# Power_Nichrome.net
KiCad netlist of a schematic drawn in Altium Designer
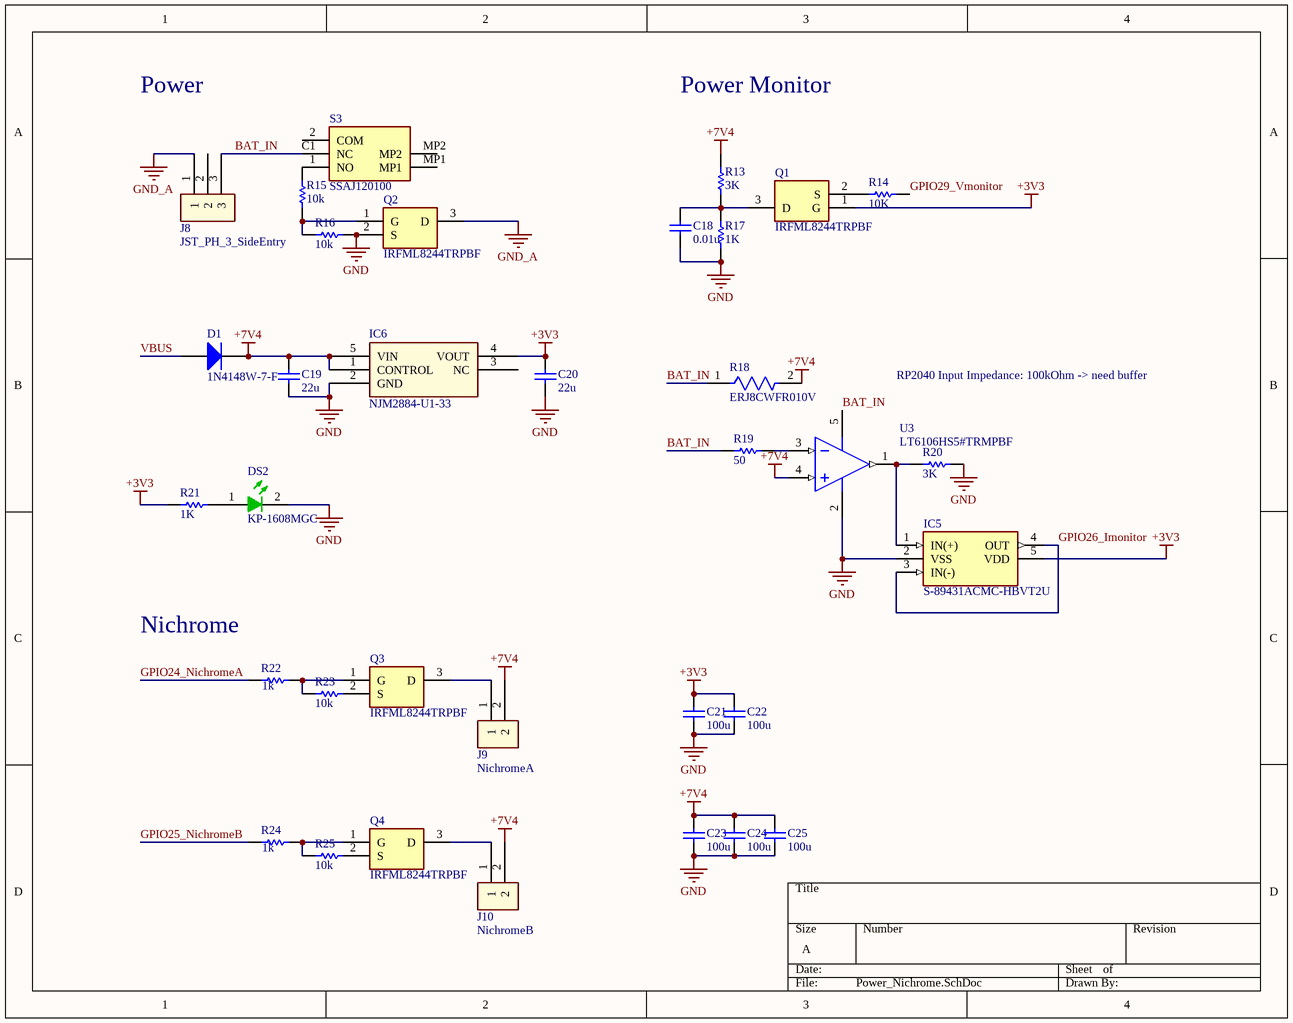
[diagram p0: Power_Nichrome.SchDoc]

(export (version "E")
  (design (tool "Eeschema 10.0.6"))
  (components
    (comp (ref "C18")
      (value "0.01u")
      (footprint "1608[0603]")
      (description "Capacitor")
      (libsource (lib "Simulation Generic Components") (part "Capacitor"))
    )
    (comp (ref "C19")
      (value "22u")
      (footprint "1608[0603]")
      (description "Capacitor")
      (libsource (lib "Simulation Generic Components") (part "Capacitor"))
    )
    (comp (ref "C20")
      (value "22u")
      (footprint "1608[0603]")
      (description "Capacitor")
      (libsource (lib "Simulation Generic Components") (part "Capacitor"))
    )
    (comp (ref "C21")
      (value "100u")
      (footprint "1608[0603]")
      (description "Capacitor")
      (libsource (lib "Simulation Generic Components") (part "Capacitor"))
    )
    (comp (ref "C22")
      (value "100u")
      (footprint "1608[0603]")
      (description "Capacitor")
      (libsource (lib "Simulation Generic Components") (part "Capacitor"))
    )
    (comp (ref "C23")
      (value "100u")
      (footprint "1608[0603]")
      (description "Capacitor")
      (libsource (lib "Simulation Generic Components") (part "Capacitor"))
    )
    (comp (ref "C24")
      (value "100u")
      (footprint "1608[0603]")
      (description "Capacitor")
      (libsource (lib "Simulation Generic Components") (part "Capacitor"))
    )
    (comp (ref "C25")
      (value "100u")
      (footprint "1608[0603]")
      (description "Capacitor")
      (libsource (lib "Simulation Generic Components") (part "Capacitor"))
    )
    (comp (ref "D1")
      (value "1N4148W-7-F")
      (footprint "DIOD-SOD123-2_V")
      (description "Fast Switching Diode, 100 V, 0.15 A, -65 to 150 degC, 2-Pin?SOD123, RoHS, Tape and Reel")
      (fields (field (name "MANUFACTURER") "DiodesIncorporated"))
      (libsource (lib "Altium Content Vault") (part "D-AK-2"))
    )
    (comp (ref "DS2")
      (value "KP-1608MGC")
      (footprint "KING-0603LED_GREEN_V")
      (description "LED, SMT, 0603(1608), 1.1mm thickness, Green")
      (fields (field (name "MANUFACTURER") "Kingbright"))
      (libsource (lib "Altium Content Vault") (part "KING-LED-GREEN-A1K2-2"))
    )
    (comp (ref "IC5")
      (value "S-89431ACMC-HBVT2U")
      (footprint "SamacSys:SOT95P275X130-5N")
      (description "Integrated Circuit")
      (fields (field (name "MOUSER PART NUMBER") "628-S89431ACMCHBVT2G"))
      (libsource (lib "*") (part "S-89431ACMC-HBVT2U"))
    )
    (comp (ref "IC6")
      (value "NJM2884-U1-33")
      (footprint "NJM2884-U1-33")
      (libsource (lib "tanekonsat_lib") (part "NJM2884-U1-33"))
    )
    (comp (ref "J8")
      (value "JST_PH_3_SideEntry")
      (footprint "JST_PH_3_SideEntry")
      (libsource (lib "tanekonsat_lib") (part "JST_PH_3_SideEntry"))
    )
    (comp (ref "J9")
      (value "NichromeA")
      (footprint "PinHeader_2.0_2_SMD")
      (libsource (lib "tanekonsat_lib") (part "PinHeader_2.0_2_SMD"))
    )
    (comp (ref "J10")
      (value "NichromeB")
      (footprint "PinHeader_2.0_2_SMD")
      (libsource (lib "tanekonsat_lib") (part "PinHeader_2.0_2_SMD"))
    )
    (comp (ref "Q1")
      (value "IRFML8244TRPBF")
      (footprint "SamacSys:SOT95P237X112-3N")
      (description "Transistor")
      (fields (field (name "MOUSER PART NUMBER") "942-IRFML8244TRPBF"))
      (libsource (lib "") (part "IRFML8244TRPBF_1"))
    )
    (comp (ref "Q2")
      (value "IRFML8244TRPBF")
      (footprint "SamacSys:SOT95P237X112-3N")
      (description "Transistor")
      (fields (field (name "MOUSER PART NUMBER") "942-IRFML8244TRPBF"))
      (libsource (lib "*") (part "IRFML8244TRPBF"))
    )
    (comp (ref "Q3")
      (value "IRFML8244TRPBF")
      (footprint "SamacSys:SOT95P237X112-3N")
      (description "Transistor")
      (fields (field (name "MOUSER PART NUMBER") "942-IRFML8244TRPBF"))
      (libsource (lib "*") (part "IRFML8244TRPBF"))
    )
    (comp (ref "Q4")
      (value "IRFML8244TRPBF")
      (footprint "SamacSys:SOT95P237X112-3N")
      (description "Transistor")
      (fields (field (name "MOUSER PART NUMBER") "942-IRFML8244TRPBF"))
      (libsource (lib "*") (part "IRFML8244TRPBF"))
    )
    (comp (ref "R13")
      (value "3K")
      (footprint "1608[0603]")
      (description "Resistor")
      (libsource (lib "Simulation Generic Components") (part "Resistor"))
    )
    (comp (ref "R14")
      (value "10K")
      (footprint "1608[0603]")
      (description "Resistor")
      (libsource (lib "Simulation Generic Components") (part "Resistor"))
    )
    (comp (ref "R15")
      (value "10k")
      (footprint "1608[0603]")
      (description "Resistor")
      (libsource (lib "Simulation Generic Components") (part "Resistor"))
    )
    (comp (ref "R16")
      (value "10k")
      (footprint "1608[0603]")
      (description "Resistor")
      (libsource (lib "Simulation Generic Components") (part "Resistor"))
    )
    (comp (ref "R17")
      (value "1K")
      (footprint "1608[0603]")
      (description "Resistor")
      (libsource (lib "Simulation Generic Components") (part "Resistor"))
    )
    (comp (ref "R18")
      (value "ERJ8CWFR010V")
      (footprint "FP-ERJ8CW-MFG")
      (description "RES 0.01 OHM 1% 1W 1206")
      (fields (field (name "TOLERANCE") "1%"))
      (libsource (lib "Altium Content Vault") (part "1029c3af85768c4190bb7ad29bc67b5"))
    )
    (comp (ref "R19")
      (value "50")
      (footprint "1608[0603]")
      (description "Resistor")
      (libsource (lib "Simulation Generic Components") (part "Resistor"))
    )
    (comp (ref "R20")
      (value "3K")
      (footprint "1608[0603]")
      (description "Resistor")
      (libsource (lib "Simulation Generic Components") (part "Resistor"))
    )
    (comp (ref "R21")
      (value "1K")
      (footprint "1608[0603]")
      (description "Resistor")
      (libsource (lib "Simulation Generic Components") (part "Resistor"))
    )
    (comp (ref "R22")
      (value "1k")
      (footprint "1608[0603]")
      (description "Resistor")
      (libsource (lib "Simulation Generic Components") (part "Resistor"))
    )
    (comp (ref "R23")
      (value "10k")
      (footprint "1608[0603]")
      (description "Resistor")
      (libsource (lib "Simulation Generic Components") (part "Resistor"))
    )
    (comp (ref "R24")
      (value "1k")
      (footprint "1608[0603]")
      (description "Resistor")
      (libsource (lib "Simulation Generic Components") (part "Resistor"))
    )
    (comp (ref "R25")
      (value "10k")
      (footprint "1608[0603]")
      (description "Resistor")
      (libsource (lib "Simulation Generic Components") (part "Resistor"))
    )
    (comp (ref "S3")
      (value "SSAJ120100")
      (footprint "SSAJ120100")
      (description "Switch")
      (fields (field (name "MOUSER PART NUMBER") "688-SSAJ120100"))
      (libsource (lib "SamacSys") (part "SSAJ120100"))
    )
    (comp (ref "U3")
      (value "LT6106HS5#TRMPBF")
      (footprint "LT-S5-5-TSOT-23_N")
      (fields
        (field (name "MANUFACTURER") "Linear Technology")
        (field (name "LINEAR TECHNOLOGY PART NUMBER") "LT6106")
      )
      (libsource (lib "Altium Content Vault") (part "LT-LT6106-LTC6101HV-5"))
    )
  )
  (nets
    (net (code "1") (name "+3V3") (class "Default")
      (node (ref "C20") (pin "2") (pinfunction "2_2") (pintype "passive"))
      (node (ref "C21") (pin "2") (pinfunction "2_2") (pintype "passive"))
      (node (ref "C22") (pin "2") (pinfunction "2_2") (pintype "passive"))
      (node (ref "IC5") (pin "5") (pinfunction "VDD_5") (pintype "power_in"))
      (node (ref "IC6") (pin "4") (pinfunction "VOUT_4") (pintype "passive"))
      (node (ref "Q1") (pin "1") (pinfunction "G_1") (pintype "passive"))
      (node (ref "R21") (pin "1") (pinfunction "1_1") (pintype "passive"))
    )
    (net (code "2") (name "+7V4") (class "Default")
      (node (ref "C19") (pin "2") (pinfunction "2_2") (pintype "passive"))
      (node (ref "C23") (pin "2") (pinfunction "2_2") (pintype "passive"))
      (node (ref "C24") (pin "2") (pinfunction "2_2") (pintype "passive"))
      (node (ref "C25") (pin "2") (pinfunction "2_2") (pintype "passive"))
      (node (ref "D1") (pin "2") (pinfunction "K_2") (pintype "passive"))
      (node (ref "IC6") (pin "1") (pinfunction "CONTROL_1") (pintype "passive"))
      (node (ref "IC6") (pin "5") (pinfunction "VIN_5") (pintype "passive"))
      (node (ref "J10") (pin "2") (pinfunction "2_2") (pintype "passive"))
      (node (ref "J9") (pin "2") (pinfunction "2_2") (pintype "passive"))
      (node (ref "R13") (pin "2") (pinfunction "2_2") (pintype "passive"))
      (node (ref "R18") (pin "2") (pinfunction "2_2") (pintype "passive"))
      (node (ref "U3") (pin "4") (pinfunction "+IN_4") (pintype "input"))
    )
    (net (code "3") (name "/BAT_IN") (class "Default")
      (node (ref "J8") (pin "3") (pinfunction "3_3") (pintype "passive"))
      (node (ref "R18") (pin "1") (pinfunction "1_1") (pintype "passive"))
      (node (ref "R19") (pin "1") (pinfunction "1_1") (pintype "passive"))
      (node (ref "S3") (pin "C1") (pinfunction "NC_C1") (pintype "passive"))
      (node (ref "U3") (pin "5") (pinfunction "V+_5") (pintype "power_in"))
    )
    (net (code "4") (name "/GPIO24_NichromeA") (class "Default")
      (node (ref "R22") (pin "1") (pinfunction "1_1") (pintype "passive"))
    )
    (net (code "5") (name "/GPIO25_NichromeB") (class "Default")
      (node (ref "R24") (pin "1") (pinfunction "1_1") (pintype "passive"))
    )
    (net (code "6") (name "/GPIO26_Imonitor") (class "Default")
      (node (ref "IC5") (pin "3") (pinfunction "IN(-)_3") (pintype "input"))
      (node (ref "IC5") (pin "4") (pinfunction "OUT_4") (pintype "output"))
    )
    (net (code "7") (name "/GPIO29_Vmonitor") (class "Default")
      (node (ref "R14") (pin "2") (pinfunction "2_2") (pintype "passive"))
    )
    (net (code "8") (name "/VBUS") (class "Default")
      (node (ref "D1") (pin "1") (pinfunction "A_1") (pintype "passive"))
    )
    (net (code "9") (name "GND") (class "Default")
      (node (ref "C18") (pin "2") (pinfunction "2_2") (pintype "passive"))
      (node (ref "C19") (pin "1") (pinfunction "1_1") (pintype "passive"))
      (node (ref "C20") (pin "1") (pinfunction "1_1") (pintype "passive"))
      (node (ref "C21") (pin "1") (pinfunction "1_1") (pintype "passive"))
      (node (ref "C22") (pin "1") (pinfunction "1_1") (pintype "passive"))
      (node (ref "C23") (pin "1") (pinfunction "1_1") (pintype "passive"))
      (node (ref "C24") (pin "1") (pinfunction "1_1") (pintype "passive"))
      (node (ref "C25") (pin "1") (pinfunction "1_1") (pintype "passive"))
      (node (ref "DS2") (pin "2") (pinfunction "K_2") (pintype "passive"))
      (node (ref "IC5") (pin "2") (pinfunction "VSS_2") (pintype "power_in"))
      (node (ref "IC6") (pin "2") (pinfunction "GND_2") (pintype "passive"))
      (node (ref "Q2") (pin "2") (pinfunction "S_2") (pintype "passive"))
      (node (ref "R16") (pin "1") (pinfunction "1_1") (pintype "passive"))
      (node (ref "R17") (pin "1") (pinfunction "1_1") (pintype "passive"))
      (node (ref "R20") (pin "2") (pinfunction "2_2") (pintype "passive"))
      (node (ref "U3") (pin "2") (pinfunction "V-_2") (pintype "power_in"))
    )
    (net (code "10") (name "GND_A") (class "Default")
      (node (ref "J8") (pin "1") (pinfunction "1_1") (pintype "passive"))
      (node (ref "Q2") (pin "3") (pinfunction "D_3") (pintype "passive"))
    )
    (net (code "11") (name "Net-(DS2-A)") (class "Default")
      (node (ref "DS2") (pin "1") (pinfunction "A_1") (pintype "passive"))
      (node (ref "R21") (pin "2") (pinfunction "2_2") (pintype "passive"))
    )
    (net (code "12") (name "Net-(IC5-IN(+))") (class "Default")
      (node (ref "IC5") (pin "1") (pinfunction "IN(+)_1") (pintype "input"))
      (node (ref "R20") (pin "1") (pinfunction "1_1") (pintype "passive"))
      (node (ref "U3") (pin "1") (pinfunction "OUT_1") (pintype "output"))
    )
    (net (code "13") (name "Net-(Q1-D)") (class "Default")
      (node (ref "C18") (pin "1") (pinfunction "1_1") (pintype "passive"))
      (node (ref "Q1") (pin "3") (pinfunction "D_3") (pintype "passive"))
      (node (ref "R13") (pin "1") (pinfunction "1_1") (pintype "passive"))
      (node (ref "R17") (pin "2") (pinfunction "2_2") (pintype "passive"))
    )
    (net (code "14") (name "Net-(Q1-S)") (class "Default")
      (node (ref "Q1") (pin "2") (pinfunction "S_2") (pintype "passive"))
      (node (ref "R14") (pin "1") (pinfunction "1_1") (pintype "passive"))
    )
    (net (code "15") (name "Net-(Q2-G)") (class "Default")
      (node (ref "Q2") (pin "1") (pinfunction "G_1") (pintype "passive"))
      (node (ref "R15") (pin "2") (pinfunction "2_2") (pintype "passive"))
      (node (ref "R16") (pin "2") (pinfunction "2_2") (pintype "passive"))
    )
    (net (code "16") (name "Net-(Q3-D)") (class "Default")
      (node (ref "J9") (pin "1") (pinfunction "1_1") (pintype "passive"))
      (node (ref "Q3") (pin "3") (pinfunction "D_3") (pintype "passive"))
    )
    (net (code "17") (name "Net-(Q3-G)") (class "Default")
      (node (ref "Q3") (pin "1") (pinfunction "G_1") (pintype "passive"))
      (node (ref "R22") (pin "2") (pinfunction "2_2") (pintype "passive"))
      (node (ref "R23") (pin "1") (pinfunction "1_1") (pintype "passive"))
    )
    (net (code "18") (name "Net-(Q4-D)") (class "Default")
      (node (ref "J10") (pin "1") (pinfunction "1_1") (pintype "passive"))
      (node (ref "Q4") (pin "3") (pinfunction "D_3") (pintype "passive"))
    )
    (net (code "19") (name "Net-(Q4-G)") (class "Default")
      (node (ref "Q4") (pin "1") (pinfunction "G_1") (pintype "passive"))
      (node (ref "R24") (pin "2") (pinfunction "2_2") (pintype "passive"))
      (node (ref "R25") (pin "1") (pinfunction "1_1") (pintype "passive"))
    )
    (net (code "20") (name "Net-(S3-NO)") (class "Default")
      (node (ref "R15") (pin "1") (pinfunction "1_1") (pintype "passive"))
      (node (ref "S3") (pin "1") (pinfunction "NO_1") (pintype "passive"))
    )
    (net (code "21") (name "Net-(U3--IN)") (class "Default")
      (node (ref "R19") (pin "2") (pinfunction "2_2") (pintype "passive"))
      (node (ref "U3") (pin "3") (pinfunction "-IN_3") (pintype "input"))
    )
    (net (code "22") (name "unconnected-(IC6-NC-Pad3)") (class "Default")
      (node (ref "IC6") (pin "3") (pinfunction "NC_3") (pintype "passive"))
    )
    (net (code "23") (name "unconnected-(J8-Pad2)") (class "Default")
      (node (ref "J8") (pin "2") (pinfunction "2_2") (pintype "passive"))
    )
    (net (code "24") (name "unconnected-(Q3-S-Pad2)") (class "Default")
      (node (ref "Q3") (pin "2") (pinfunction "S_2") (pintype "passive"))
    )
    (net (code "25") (name "unconnected-(Q4-S-Pad2)") (class "Default")
      (node (ref "Q4") (pin "2") (pinfunction "S_2") (pintype "passive"))
    )
    (net (code "26") (name "unconnected-(R23-Pad2)") (class "Default")
      (node (ref "R23") (pin "2") (pinfunction "2_2") (pintype "passive"))
    )
    (net (code "27") (name "unconnected-(R25-Pad2)") (class "Default")
      (node (ref "R25") (pin "2") (pinfunction "2_2") (pintype "passive"))
    )
    (net (code "28") (name "unconnected-(S3-COM-Pad2)") (class "Default")
      (node (ref "S3") (pin "2") (pinfunction "COM_2") (pintype "passive"))
    )
    (net (code "29") (name "unconnected-(S3-PadMP1)") (class "Default")
      (node (ref "S3") (pin "MP1") (pinfunction "MP1_MP1") (pintype "passive"))
    )
    (net (code "30") (name "unconnected-(S3-PadMP2)") (class "Default")
      (node (ref "S3") (pin "MP2") (pinfunction "MP2_MP2") (pintype "passive"))
    )
  )
)
